# USB_FTDI.net
KiCad netlist of a schematic drawn in Altium Designer
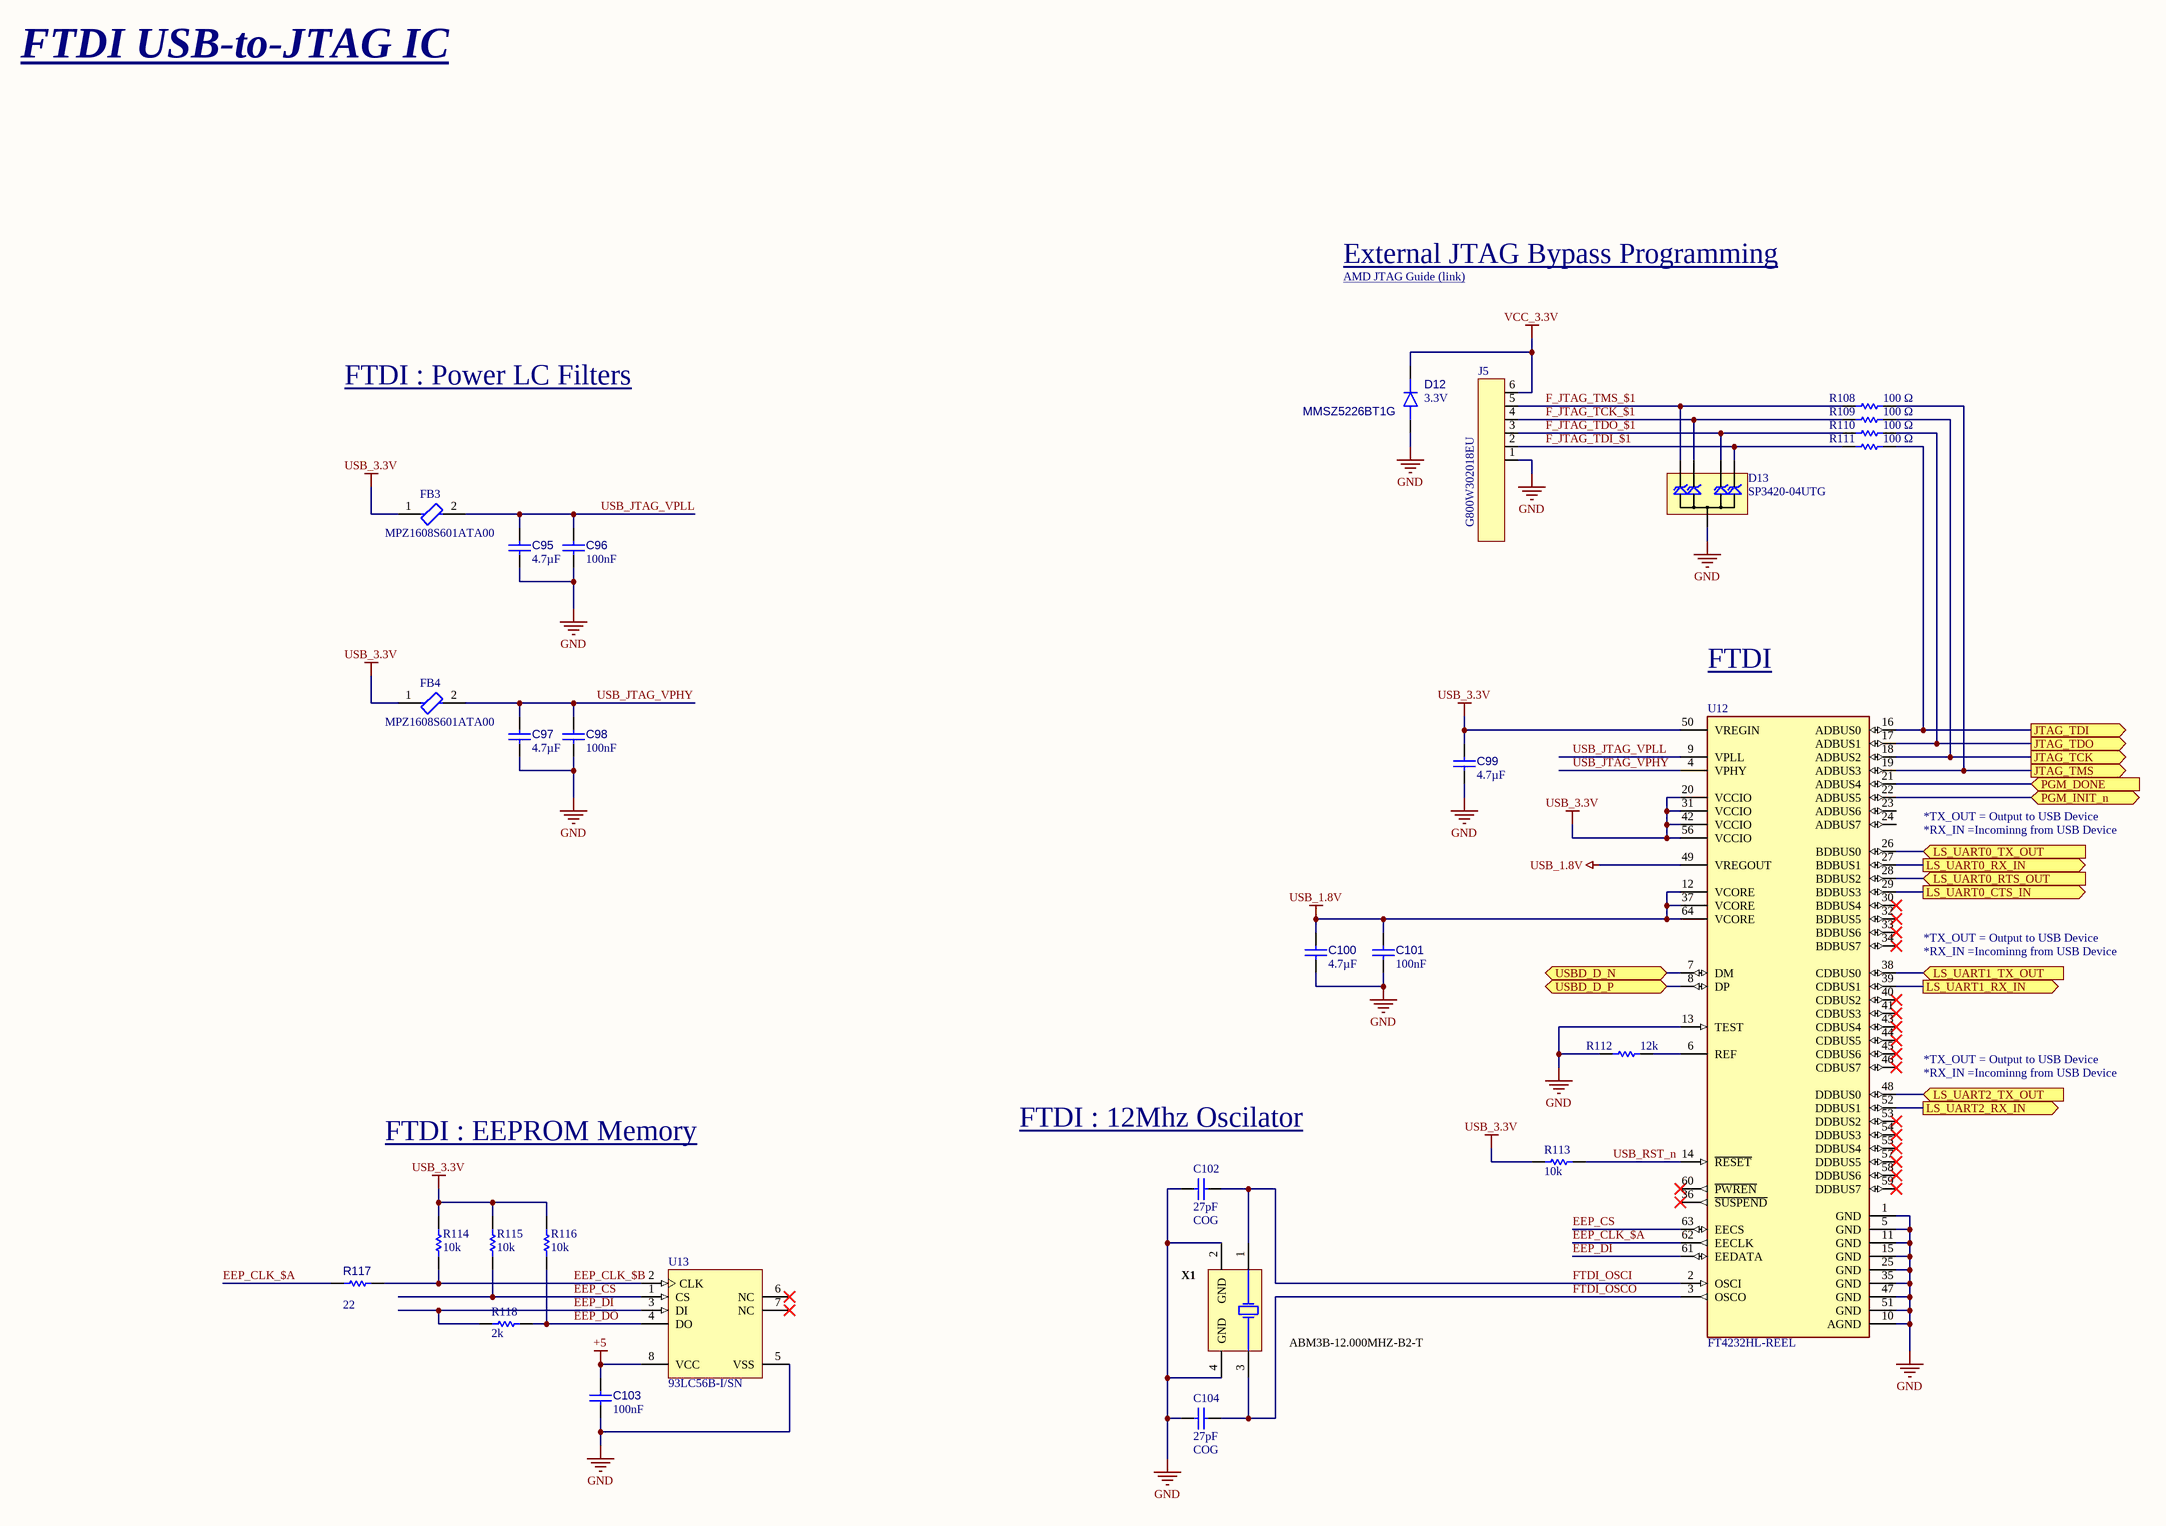
[diagram p0: USB_FTDI.SchDoc]

(export (version "E")
  (design (tool "Eeschema 10.0.6"))
  (components
    (comp (ref "C95")
      (value "4.7µF")
      (footprint "CAPC0603(1608)100_L")
      (description "Chip Capacitor, 4.7µF +/-20%, 10V, 0603, Thickness 1 mm")
      (fields (field (name "TOLERANCE") "10%") (field (name "Comment") "Capacitor 4.7µF +/-20% 10V 0603"))
      (libsource (lib "Personal Workspace") (part "CAP-NP-2"))
    )
    (comp (ref "C96")
      (value "100nF")
      (footprint "CAPC1005X56X25LL10T15")
      (description "Chip Capacitor, 0.1 uF, +/- 5%, 16 V, 0402 (1005 Metric)")
      (fields (field (name "TOLERANCE") "5%") (field (name "Comment") "Capacitor 0.1 uF +/- 5% 16 V 0402"))
      (libsource (lib "Personal Workspace") (part "CAP-NP-2"))
    )
    (comp (ref "C97")
      (value "4.7µF")
      (footprint "CAPC0603(1608)100_L")
      (description "Chip Capacitor, 4.7µF +/-20%, 10V, 0603, Thickness 1 mm")
      (fields (field (name "TOLERANCE") "10%") (field (name "Comment") "Capacitor 4.7µF +/-20% 10V 0603"))
      (libsource (lib "Personal Workspace") (part "CAP-NP-2"))
    )
    (comp (ref "C98")
      (value "100nF")
      (footprint "CAPC1005X56X25LL10T15")
      (description "Chip Capacitor, 0.1 uF, +/- 5%, 16 V, 0402 (1005 Metric)")
      (fields (field (name "TOLERANCE") "5%") (field (name "Comment") "Capacitor 0.1 uF +/- 5% 16 V 0402"))
      (libsource (lib "Personal Workspace") (part "CAP-NP-2"))
    )
    (comp (ref "C99")
      (value "4.7µF")
      (footprint "CAPC0603(1608)100_L")
      (description "Chip Capacitor, 4.7µF +/-20%, 10V, 0603, Thickness 1 mm")
      (fields (field (name "TOLERANCE") "10%") (field (name "Comment") "Capacitor 4.7µF +/-20% 10V 0603"))
      (libsource (lib "Personal Workspace") (part "CAP-NP-2"))
    )
    (comp (ref "C100")
      (value "4.7µF")
      (footprint "CAPC0603(1608)100_L")
      (description "Chip Capacitor, 4.7µF +/-20%, 10V, 0603, Thickness 1 mm")
      (fields (field (name "TOLERANCE") "10%") (field (name "Comment") "Capacitor 4.7µF +/-20% 10V 0603"))
      (libsource (lib "Personal Workspace") (part "CAP-NP-2"))
    )
    (comp (ref "C101")
      (value "100nF")
      (footprint "CAPC1005X56X25LL10T15")
      (description "Chip Capacitor, 0.1 uF, +/- 5%, 16 V, 0402 (1005 Metric)")
      (fields (field (name "TOLERANCE") "5%") (field (name "Comment") "Capacitor 0.1 uF +/- 5% 16 V 0402"))
      (libsource (lib "Personal Workspace") (part "CAP-NP-2"))
    )
    (comp (ref "C102")
      (value "27pF")
      (footprint "FP-C0402-BB-MFG")
      (fields (field (name "CAPACITOR MATERIAL TYPE") "COG") (field (name "Comment") "C0402C270F5GACTU"))
      (libsource (lib "Personal Workspace") (part "CAP-NP-2"))
    )
    (comp (ref "C103")
      (value "100nF")
      (footprint "CAPC1005X56X25LL10T15")
      (description "Chip Capacitor, 0.1 uF, +/- 5%, 16 V, 0402 (1005 Metric)")
      (fields (field (name "TOLERANCE") "5%") (field (name "Comment") "Capacitor 0.1 uF +/- 5% 16 V 0402"))
      (libsource (lib "Personal Workspace") (part "CAP-NP-2"))
    )
    (comp (ref "C104")
      (value "27pF")
      (footprint "FP-C0402-BB-MFG")
      (fields (field (name "CAPACITOR MATERIAL TYPE") "COG") (field (name "Comment") "C0402C270F5GACTU"))
      (libsource (lib "Personal Workspace") (part "CAP-NP-2"))
    )
    (comp (ref "D12")
      (value "MMSZ5226BT1G")
      (description "Zener Diode, 3.3V V(Z), 5%, 0.5W, Silicon, Unidirectional")
      (fields (field (name "FORWARD VOLTAGE") "3.3V"))
      (libsource (lib "Personal Workspace") (part "DIODE-2"))
    )
    (comp (ref "D13")
      (value "SP3420-04UTG")
      (footprint "uDFN-10")
      (description "TVS Diode Array Low Capacitance ESD Protection 4-Channel (Vwork=3V3, Vclamp=6V)")
      (fields
        (field (name "MANUFACTURER") "Littelfuse")
        (field (name "SOURCE") "Schematic-Lib-PhilsLab.SchLib")
      )
      (libsource (lib "Personal Workspace") (part "SP3420-04UTG"))
    )
    (comp (ref "FB3")
      (value "MPZ1608S601ATA00")
      (footprint "FP-MPZ1608-0_8-MFG")
      (description "Power line Ferrite Bead 600Ω @ 100MHz 1A DCR 0.15Ω SMD 0603")
      (fields (field (name "TOLERANCE") "25%"))
      (libsource (lib "Altium Content Vault") (part "5f30dd21d616792df468990f7003faa"))
    )
    (comp (ref "FB4")
      (value "MPZ1608S601ATA00")
      (footprint "FP-MPZ1608-0_8-MFG")
      (description "Power line Ferrite Bead 600Ω @ 100MHz 1A DCR 0.15Ω SMD 0603")
      (fields (field (name "TOLERANCE") "25%"))
      (libsource (lib "Altium Content Vault") (part "5f30dd21d616792df468990f7003faa"))
    )
    (comp (ref "J5")
      (value "G800W302018EU")
      (footprint "G800W302018EU")
      (description "Pin Header 6 Position 2.54mm Pitch")
      (fields
        (field (name "MANUFACTURER") "Amphenol")
        (field (name "SOURCE") "Schematic-Lib-PhilsLab.SchLib")
      )
      (libsource (lib "Personal Workspace") (part "801-87-006-10-012101"))
    )
    (comp (ref "R108")
      (value "100 Ω")
      (footprint "RESC1608X55X30LL15T15")
      (fields (field (name "MANUFACTURER") "Panasonic") (field (name "PART NUMBER") "ERJ-3EKF1000V"))
      (libsource (lib "Altium Content Vault") (part "RES"))
    )
    (comp (ref "R109")
      (value "100 Ω")
      (footprint "RESC1608X55X30LL15T15")
      (fields (field (name "MANUFACTURER") "Panasonic") (field (name "PART NUMBER") "ERJ-3EKF1000V"))
      (libsource (lib "Altium Content Vault") (part "RES"))
    )
    (comp (ref "R110")
      (value "100 Ω")
      (footprint "RESC1608X55X30LL15T15")
      (fields (field (name "MANUFACTURER") "Panasonic") (field (name "PART NUMBER") "ERJ-3EKF1000V"))
      (libsource (lib "Altium Content Vault") (part "RES"))
    )
    (comp (ref "R111")
      (value "100 Ω")
      (footprint "RESC1608X55X30LL15T15")
      (fields (field (name "MANUFACTURER") "Panasonic") (field (name "PART NUMBER") "ERJ-3EKF1000V"))
      (libsource (lib "Altium Content Vault") (part "RES"))
    )
    (comp (ref "R112")
      (value "12k")
      (footprint "RESC0402(1005)_L")
      (description "Chip Resistor, 12 kOhms, +/-1 %, 63 mW, -55 to 155 degC, 0402")
      (fields (field (name "POWER") "63mW") (field (name "TOLERANCE") "1%"))
      (libsource (lib "Personal Workspace") (part "RES"))
    )
    (comp (ref "R113")
      (value "10k")
      (footprint "RESC1005X40X25ML05T05")
      (description "Chip Resistor, 10 KOhm, +/- 1%, 63 mW, -55 to 155 degC, 0402 (1005 Metric)")
      (fields (field (name "TOLERANCE") "1%") (field (name "POWER") "63mW"))
      (libsource (lib "Personal Workspace") (part "RES-2"))
    )
    (comp (ref "R114")
      (value "10k")
      (footprint "RESC1005X40X25ML05T05")
      (description "Chip Resistor, 10 KOhm, +/- 1%, 63 mW, -55 to 155 degC, 0402 (1005 Metric)")
      (fields (field (name "TOLERANCE") "1%") (field (name "POWER") "63mW"))
      (libsource (lib "Personal Workspace") (part "RES"))
    )
    (comp (ref "R115")
      (value "10k")
      (footprint "RESC1005X40X25ML05T05")
      (description "Chip Resistor, 10 KOhm, +/- 1%, 63 mW, -55 to 155 degC, 0402 (1005 Metric)")
      (fields (field (name "TOLERANCE") "1%") (field (name "POWER") "63mW"))
      (libsource (lib "Personal Workspace") (part "RES"))
    )
    (comp (ref "R116")
      (value "10k")
      (footprint "RESC1005X40X25ML05T05")
      (description "Chip Resistor, 10 KOhm, +/- 1%, 63 mW, -55 to 155 degC, 0402 (1005 Metric)")
      (fields (field (name "TOLERANCE") "1%") (field (name "POWER") "63mW"))
      (libsource (lib "Personal Workspace") (part "RES"))
    )
    (comp (ref "R117")
      (value "22")
      (footprint "RESC0402(1005)_L")
      (description "22R 0.063W 5% 0402 (1005 Metric)  SMD")
      (fields (field (name "TOLERANCE") "5%") (field (name "POWER") "63mW"))
      (libsource (lib "") (part "RES-2_1"))
    )
    (comp (ref "R118")
      (value "2k")
      (footprint "RESC0402(1005)_L")
      (description "Chip Resistor, 2 kOhms, +/-5 %, 63 mW, -55 to 155 degC, 0402")
      (fields (field (name "TOLERANCE") "5%") (field (name "POWER") "63mW"))
      (libsource (lib "Personal Workspace") (part "RES"))
    )
    (comp (ref "U12")
      (value "FT4232HL-REEL")
      (footprint "FP-LQFP-64-IPC_A")
      (description "Serial I/O Controller, 4 Channel(s), 1.5MBps, CMOS, PQFP64")
      (libsource (lib "Personal Workspace") (part "5175c878c9adaddaac9be39d59efec7"))
    )
    (comp (ref "U13")
      (value "93LC56B-I/SN")
      (footprint "SOIC-SN8_L")
      (description "2K, 128x16-bit, 2.5V Microwire Serial EEPROM, 8-Pin SOIC 150mil, Industrial Temperature")
      (libsource (lib "Altium Content Vault") (part "MEM-SEEPROM-93AA46B-P-8"))
    )
    (comp (ref "X1")
      (value "ABM3B-12.000MHZ-B2-T")
      (footprint "ABRA-ABM3B-4_V")
      (description "Ceramic SMD Crystal, 12 MHz, +/- 20 ppm, 18 pF, -20 to 70 degC, 4-Pin SMD, RoHS, Tape and Reel")
      (fields (field (name "TOLERANCE") "20ppm") (field (name "MANUFACTURER") "Abracon"))
      (libsource (lib "Personal Workspace") (part "XTAL-1-3-4"))
    )
  )
  (nets
    (net (code "1") (name "+5") (class "Default")
      (node (ref "C103") (pin "2") (pinfunction "2_2") (pintype "passive"))
      (node (ref "U13") (pin "8") (pinfunction "VCC_8") (pintype "power_in"))
    )
    (net (code "2") (name "/EEP_CLK_$A") (class "Default")
      (node (ref "R117") (pin "1") (pinfunction "1_1") (pintype "passive"))
      (node (ref "U12") (pin "62") (pinfunction "EECLK_62") (pintype "output"))
    )
    (net (code "3") (name "/EEP_CLK_$B") (class "Default")
      (node (ref "R114") (pin "1") (pinfunction "1_1") (pintype "passive"))
      (node (ref "R117") (pin "2") (pinfunction "2_2") (pintype "passive"))
      (node (ref "U13") (pin "2") (pinfunction "CLK_2") (pintype "input"))
    )
    (net (code "4") (name "/EEP_CS") (class "Default")
      (node (ref "R115") (pin "1") (pinfunction "1_1") (pintype "passive"))
      (node (ref "U12") (pin "63") (pinfunction "EECS_63") (pintype "bidirectional"))
      (node (ref "U13") (pin "1") (pinfunction "CS_1") (pintype "input"))
    )
    (net (code "5") (name "/EEP_DI") (class "Default")
      (node (ref "R118") (pin "2") (pinfunction "2_2") (pintype "passive"))
      (node (ref "U12") (pin "61") (pinfunction "EEDATA_61") (pintype "bidirectional"))
      (node (ref "U13") (pin "3") (pinfunction "DI_3") (pintype "input"))
    )
    (net (code "6") (name "/EEP_DO") (class "Default")
      (node (ref "R116") (pin "1") (pinfunction "1_1") (pintype "passive"))
      (node (ref "R118") (pin "1") (pinfunction "1_1") (pintype "passive"))
      (node (ref "U13") (pin "4") (pinfunction "DO_4") (pintype "tri_state"))
    )
    (net (code "7") (name "/FTDI_OSCI") (class "Default")
      (node (ref "C102") (pin "1") (pinfunction "1_1") (pintype "passive"))
      (node (ref "U12") (pin "2") (pinfunction "OSCI_2") (pintype "input"))
      (node (ref "X1") (pin "1") (pinfunction "X1_1") (pintype "passive"))
    )
    (net (code "8") (name "/FTDI_OSCO") (class "Default")
      (node (ref "C104") (pin "1") (pinfunction "1_1") (pintype "passive"))
      (node (ref "U12") (pin "3") (pinfunction "OSCO_3") (pintype "output"))
      (node (ref "X1") (pin "3") (pinfunction "X2_3") (pintype "passive"))
    )
    (net (code "9") (name "/F_JTAG_TCK_$1") (class "Default")
      (node (ref "D13") (pin "29") (pintype "passive"))
      (node (ref "J5") (pin "4") (pinfunction "4_4") (pintype "passive"))
      (node (ref "R109") (pin "1") (pinfunction "1_1") (pintype "passive"))
    )
    (net (code "10") (name "/F_JTAG_TDI_$1") (class "Default")
      (node (ref "D13") (pin "56") (pintype "passive"))
      (node (ref "J5") (pin "2") (pinfunction "2_2") (pintype "passive"))
      (node (ref "R111") (pin "1") (pinfunction "1_1") (pintype "passive"))
    )
    (net (code "11") (name "/F_JTAG_TDO_$1") (class "Default")
      (node (ref "D13") (pin "47") (pintype "passive"))
      (node (ref "J5") (pin "3") (pinfunction "3_3") (pintype "passive"))
      (node (ref "R110") (pin "1") (pinfunction "1_1") (pintype "passive"))
    )
    (net (code "12") (name "/F_JTAG_TMS_$1") (class "Default")
      (node (ref "D13") (pin "110") (pintype "passive"))
      (node (ref "J5") (pin "5") (pinfunction "5_5") (pintype "passive"))
      (node (ref "R108") (pin "1") (pinfunction "1_1") (pintype "passive"))
    )
    (net (code "13") (name "/JTAG_TCK") (class "Default")
      (node (ref "R109") (pin "2") (pinfunction "2_2") (pintype "passive"))
      (node (ref "U12") (pin "18") (pinfunction "ADBUS2_18") (pintype "bidirectional"))
    )
    (net (code "14") (name "/JTAG_TDI") (class "Default")
      (node (ref "R111") (pin "2") (pinfunction "2_2") (pintype "passive"))
      (node (ref "U12") (pin "16") (pinfunction "ADBUS0_16") (pintype "bidirectional"))
    )
    (net (code "15") (name "/JTAG_TDO") (class "Default")
      (node (ref "R110") (pin "2") (pinfunction "2_2") (pintype "passive"))
      (node (ref "U12") (pin "17") (pinfunction "ADBUS1_17") (pintype "bidirectional"))
    )
    (net (code "16") (name "/JTAG_TMS") (class "Default")
      (node (ref "R108") (pin "2") (pinfunction "2_2") (pintype "passive"))
      (node (ref "U12") (pin "19") (pinfunction "ADBUS3_19") (pintype "bidirectional"))
    )
    (net (code "17") (name "/LS_UART0_CTS_IN") (class "Default")
      (node (ref "U12") (pin "29") (pinfunction "BDBUS3_29") (pintype "bidirectional"))
    )
    (net (code "18") (name "/LS_UART0_RTS_OUT") (class "Default")
      (node (ref "U12") (pin "28") (pinfunction "BDBUS2_28") (pintype "bidirectional"))
    )
    (net (code "19") (name "/LS_UART0_RX_IN") (class "Default")
      (node (ref "U12") (pin "27") (pinfunction "BDBUS1_27") (pintype "bidirectional"))
    )
    (net (code "20") (name "/LS_UART0_TX_OUT") (class "Default")
      (node (ref "U12") (pin "26") (pinfunction "BDBUS0_26") (pintype "bidirectional"))
    )
    (net (code "21") (name "/LS_UART1_RX_IN") (class "Default")
      (node (ref "U12") (pin "39") (pinfunction "CDBUS1_39") (pintype "bidirectional"))
    )
    (net (code "22") (name "/LS_UART1_TX_OUT") (class "Default")
      (node (ref "U12") (pin "38") (pinfunction "CDBUS0_38") (pintype "bidirectional"))
    )
    (net (code "23") (name "/LS_UART2_RX_IN") (class "Default")
      (node (ref "U12") (pin "52") (pinfunction "DDBUS1_52") (pintype "bidirectional"))
    )
    (net (code "24") (name "/LS_UART2_TX_OUT") (class "Default")
      (node (ref "U12") (pin "48") (pinfunction "DDBUS0_48") (pintype "bidirectional"))
    )
    (net (code "25") (name "/PGM_DONE") (class "Default")
      (node (ref "U12") (pin "21") (pinfunction "ADBUS4_21") (pintype "bidirectional"))
    )
    (net (code "26") (name "/PGM_INIT_n") (class "Default")
      (node (ref "U12") (pin "22") (pinfunction "ADBUS5_22") (pintype "bidirectional"))
    )
    (net (code "27") (name "/USBD_D_N") (class "Default")
      (node (ref "U12") (pin "7") (pinfunction "DM_7") (pintype "bidirectional"))
    )
    (net (code "28") (name "/USBD_D_P") (class "Default")
      (node (ref "U12") (pin "8") (pinfunction "DP_8") (pintype "bidirectional"))
    )
    (net (code "29") (name "/USB_JTAG_VPHY") (class "Default")
      (node (ref "C97") (pin "2") (pinfunction "2_2") (pintype "passive"))
      (node (ref "C98") (pin "2") (pinfunction "2_2") (pintype "passive"))
      (node (ref "FB4") (pin "2") (pinfunction "2_2") (pintype "passive"))
      (node (ref "U12") (pin "4") (pinfunction "VPHY_4") (pintype "power_in"))
    )
    (net (code "30") (name "/USB_JTAG_VPLL") (class "Default")
      (node (ref "C95") (pin "2") (pinfunction "2_2") (pintype "passive"))
      (node (ref "C96") (pin "2") (pinfunction "2_2") (pintype "passive"))
      (node (ref "FB3") (pin "2") (pinfunction "2_2") (pintype "passive"))
      (node (ref "U12") (pin "9") (pinfunction "VPLL_9") (pintype "power_in"))
    )
    (net (code "31") (name "/USB_RST_n") (class "Default")
      (node (ref "R113") (pin "1") (pinfunction "1_1") (pintype "passive"))
      (node (ref "U12") (pin "14") (pinfunction "~{RESET}_14") (pintype "input"))
    )
    (net (code "32") (name "GND") (class "Default")
      (node (ref "C100") (pin "1") (pinfunction "1_1") (pintype "passive"))
      (node (ref "C101") (pin "1") (pinfunction "1_1") (pintype "passive"))
      (node (ref "C102") (pin "2") (pinfunction "2_2") (pintype "passive"))
      (node (ref "C103") (pin "1") (pinfunction "1_1") (pintype "passive"))
      (node (ref "C104") (pin "2") (pinfunction "2_2") (pintype "passive"))
      (node (ref "C95") (pin "1") (pinfunction "1_1") (pintype "passive"))
      (node (ref "C96") (pin "1") (pinfunction "1_1") (pintype "passive"))
      (node (ref "C97") (pin "1") (pinfunction "1_1") (pintype "passive"))
      (node (ref "C98") (pin "1") (pinfunction "1_1") (pintype "passive"))
      (node (ref "C99") (pin "1") (pinfunction "1_1") (pintype "passive"))
      (node (ref "D12") (pin "2") (pinfunction "A_2") (pintype "passive"))
      (node (ref "D13") (pin "38") (pinfunction "GND_38") (pintype "passive"))
      (node (ref "J5") (pin "1") (pinfunction "1_1") (pintype "passive"))
      (node (ref "R112") (pin "1") (pinfunction "1_1") (pintype "passive"))
      (node (ref "U12") (pin "1") (pinfunction "GND_1") (pintype "power_in"))
      (node (ref "U12") (pin "10") (pinfunction "AGND_10") (pintype "power_in"))
      (node (ref "U12") (pin "11") (pinfunction "GND_11") (pintype "power_in"))
      (node (ref "U12") (pin "13") (pinfunction "TEST_13") (pintype "input"))
      (node (ref "U12") (pin "15") (pinfunction "GND_15") (pintype "power_in"))
      (node (ref "U12") (pin "25") (pinfunction "GND_25") (pintype "power_in"))
      (node (ref "U12") (pin "35") (pinfunction "GND_35") (pintype "power_in"))
      (node (ref "U12") (pin "47") (pinfunction "GND_47") (pintype "power_in"))
      (node (ref "U12") (pin "5") (pinfunction "GND_5") (pintype "power_in"))
      (node (ref "U12") (pin "51") (pinfunction "GND_51") (pintype "power_in"))
      (node (ref "U13") (pin "5") (pinfunction "VSS_5") (pintype "power_in"))
      (node (ref "X1") (pin "2") (pinfunction "GND_2") (pintype "power_in"))
      (node (ref "X1") (pin "4") (pinfunction "GND_4") (pintype "power_in"))
    )
    (net (code "33") (name "Net-(U12-REF)") (class "Default")
      (node (ref "R112") (pin "2") (pinfunction "2_2") (pintype "passive"))
      (node (ref "U12") (pin "6") (pinfunction "REF_6") (pintype "passive"))
    )
    (net (code "34") (name "USB_1.8V") (class "Default")
      (node (ref "C100") (pin "2") (pinfunction "2_2") (pintype "passive"))
      (node (ref "C101") (pin "2") (pinfunction "2_2") (pintype "passive"))
      (node (ref "U12") (pin "12") (pinfunction "VCORE_12") (pintype "power_in"))
      (node (ref "U12") (pin "37") (pinfunction "VCORE_37") (pintype "power_in"))
      (node (ref "U12") (pin "49") (pinfunction "VREGOUT_49") (pintype "power_in"))
      (node (ref "U12") (pin "64") (pinfunction "VCORE_64") (pintype "power_in"))
    )
    (net (code "35") (name "USB_3.3V") (class "Default")
      (node (ref "C99") (pin "2") (pinfunction "2_2") (pintype "passive"))
      (node (ref "FB3") (pin "1") (pinfunction "1_1") (pintype "passive"))
      (node (ref "FB4") (pin "1") (pinfunction "1_1") (pintype "passive"))
      (node (ref "R113") (pin "2") (pinfunction "2_2") (pintype "passive"))
      (node (ref "R114") (pin "2") (pinfunction "2_2") (pintype "passive"))
      (node (ref "R115") (pin "2") (pinfunction "2_2") (pintype "passive"))
      (node (ref "R116") (pin "2") (pinfunction "2_2") (pintype "passive"))
      (node (ref "U12") (pin "20") (pinfunction "VCCIO_20") (pintype "power_in"))
      (node (ref "U12") (pin "31") (pinfunction "VCCIO_31") (pintype "power_in"))
      (node (ref "U12") (pin "42") (pinfunction "VCCIO_42") (pintype "power_in"))
      (node (ref "U12") (pin "50") (pinfunction "VREGIN_50") (pintype "power_in"))
      (node (ref "U12") (pin "56") (pinfunction "VCCIO_56") (pintype "power_in"))
    )
    (net (code "36") (name "VCC_3.3V") (class "Default")
      (node (ref "D12") (pin "1") (pinfunction "K_1") (pintype "passive"))
      (node (ref "J5") (pin "6") (pinfunction "6_6") (pintype "passive"))
    )
    (net (code "37") (name "unconnected-(U12-ADBUS6-Pad23)") (class "Default")
      (node (ref "U12") (pin "23") (pinfunction "ADBUS6_23") (pintype "bidirectional"))
    )
    (net (code "38") (name "unconnected-(U12-ADBUS7-Pad24)") (class "Default")
      (node (ref "U12") (pin "24") (pinfunction "ADBUS7_24") (pintype "bidirectional"))
    )
    (net (code "39") (name "unconnected-(U12-BDBUS4-Pad30)") (class "Default")
      (node (ref "U12") (pin "30") (pinfunction "BDBUS4_30") (pintype "bidirectional+no_connect"))
    )
    (net (code "40") (name "unconnected-(U12-BDBUS5-Pad32)") (class "Default")
      (node (ref "U12") (pin "32") (pinfunction "BDBUS5_32") (pintype "bidirectional+no_connect"))
    )
    (net (code "41") (name "unconnected-(U12-BDBUS6-Pad33)") (class "Default")
      (node (ref "U12") (pin "33") (pinfunction "BDBUS6_33") (pintype "bidirectional+no_connect"))
    )
    (net (code "42") (name "unconnected-(U12-BDBUS7-Pad34)") (class "Default")
      (node (ref "U12") (pin "34") (pinfunction "BDBUS7_34") (pintype "bidirectional+no_connect"))
    )
    (net (code "43") (name "unconnected-(U12-CDBUS2-Pad40)") (class "Default")
      (node (ref "U12") (pin "40") (pinfunction "CDBUS2_40") (pintype "bidirectional+no_connect"))
    )
    (net (code "44") (name "unconnected-(U12-CDBUS3-Pad41)") (class "Default")
      (node (ref "U12") (pin "41") (pinfunction "CDBUS3_41") (pintype "bidirectional+no_connect"))
    )
    (net (code "45") (name "unconnected-(U12-CDBUS4-Pad43)") (class "Default")
      (node (ref "U12") (pin "43") (pinfunction "CDBUS4_43") (pintype "bidirectional+no_connect"))
    )
    (net (code "46") (name "unconnected-(U12-CDBUS5-Pad44)") (class "Default")
      (node (ref "U12") (pin "44") (pinfunction "CDBUS5_44") (pintype "bidirectional+no_connect"))
    )
    (net (code "47") (name "unconnected-(U12-CDBUS6-Pad45)") (class "Default")
      (node (ref "U12") (pin "45") (pinfunction "CDBUS6_45") (pintype "bidirectional+no_connect"))
    )
    (net (code "48") (name "unconnected-(U12-CDBUS7-Pad46)") (class "Default")
      (node (ref "U12") (pin "46") (pinfunction "CDBUS7_46") (pintype "bidirectional+no_connect"))
    )
    (net (code "49") (name "unconnected-(U12-DDBUS2-Pad53)") (class "Default")
      (node (ref "U12") (pin "53") (pinfunction "DDBUS2_53") (pintype "bidirectional+no_connect"))
    )
    (net (code "50") (name "unconnected-(U12-DDBUS3-Pad54)") (class "Default")
      (node (ref "U12") (pin "54") (pinfunction "DDBUS3_54") (pintype "bidirectional+no_connect"))
    )
    (net (code "51") (name "unconnected-(U12-DDBUS4-Pad55)") (class "Default")
      (node (ref "U12") (pin "55") (pinfunction "DDBUS4_55") (pintype "bidirectional+no_connect"))
    )
    (net (code "52") (name "unconnected-(U12-DDBUS5-Pad57)") (class "Default")
      (node (ref "U12") (pin "57") (pinfunction "DDBUS5_57") (pintype "bidirectional+no_connect"))
    )
    (net (code "53") (name "unconnected-(U12-DDBUS6-Pad58)") (class "Default")
      (node (ref "U12") (pin "58") (pinfunction "DDBUS6_58") (pintype "bidirectional+no_connect"))
    )
    (net (code "54") (name "unconnected-(U12-DDBUS7-Pad59)") (class "Default")
      (node (ref "U12") (pin "59") (pinfunction "DDBUS7_59") (pintype "bidirectional+no_connect"))
    )
    (net (code "55") (name "unconnected-(U12-~{PWREN}-Pad60)") (class "Default")
      (node (ref "U12") (pin "60") (pinfunction "~{PWREN}_60") (pintype "output+no_connect"))
    )
    (net (code "56") (name "unconnected-(U12-~{SUSPEND}-Pad36)") (class "Default")
      (node (ref "U12") (pin "36") (pinfunction "~{SUSPEND}_36") (pintype "output+no_connect"))
    )
    (net (code "57") (name "unconnected-(U13-NC-Pad6)") (class "Default")
      (node (ref "U13") (pin "6") (pinfunction "NC_6") (pintype "passive+no_connect"))
    )
    (net (code "58") (name "unconnected-(U13-NC-Pad7)") (class "Default")
      (node (ref "U13") (pin "7") (pinfunction "NC_7") (pintype "passive+no_connect"))
    )
  )
)
